# TFTBackpack.net
KiCad netlist of a schematic drawn in EAGLE
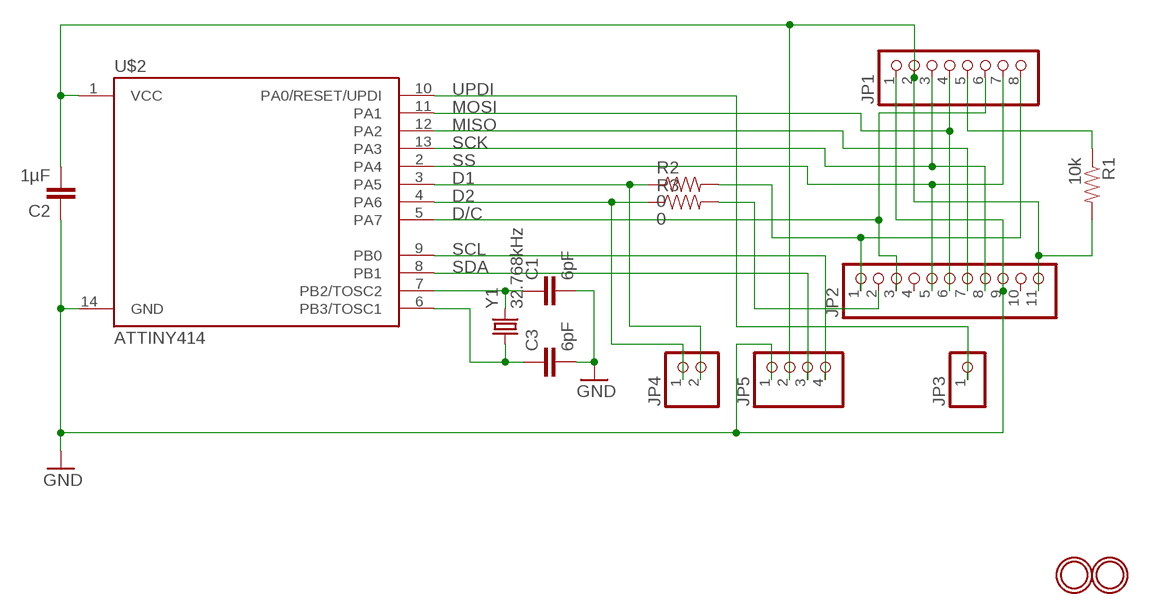
[diagram p0: schematic, sheet 1]

(export (version "E")
  (design (tool "Eeschema 10.0.6"))
  (components
    (comp (ref "C1")
      (value "6pF")
      (footprint "eagle-import:0805")
      (libsource (lib "eagle-import") (part "CAP0805"))
    )
    (comp (ref "C2")
      (value "1µF")
      (footprint "eagle-import:0805")
      (libsource (lib "eagle-import") (part "CAP0805"))
    )
    (comp (ref "C3")
      (value "6pF")
      (footprint "eagle-import:0805")
      (libsource (lib "eagle-import") (part "CAP0805"))
    )
    (comp (ref "JP1")
      (value "HEADER-1X8ROUND")
      (footprint "eagle-import:1X08_ROUND")
      (libsource (lib "eagle-import") (part "HEADER-1X8ROUND"))
    )
    (comp (ref "JP2")
      (value "HEADER-1X11")
      (footprint "eagle-import:1X11_ROUND")
      (libsource (lib "eagle-import") (part "HEADER-1X11"))
    )
    (comp (ref "JP3")
      (value "HEADER-1X1ROUND")
      (footprint "eagle-import:1X01_ROUND")
      (libsource (lib "eagle-import") (part "HEADER-1X1ROUND"))
    )
    (comp (ref "JP4")
      (value "HEADER-1X2ROUND")
      (footprint "eagle-import:1X02_ROUND")
      (libsource (lib "eagle-import") (part "HEADER-1X2ROUND"))
    )
    (comp (ref "JP5")
      (value "HEADER-1X4ROUND")
      (footprint "eagle-import:1X04_ROUND")
      (libsource (lib "eagle-import") (part "HEADER-1X4ROUND"))
    )
    (comp (ref "R1")
      (value "10k")
      (footprint "eagle-import:0805")
      (libsource (lib "eagle-import") (part "0.3OHM-1/8W-1%(0805)"))
    )
    (comp (ref "R2")
      (value "0")
      (footprint "eagle-import:0805")
      (libsource (lib "eagle-import") (part "0.3OHM-1/8W-1%(0805)"))
    )
    (comp (ref "R3")
      (value "0")
      (footprint "eagle-import:0805")
      (libsource (lib "eagle-import") (part "0.3OHM-1/8W-1%(0805)"))
    )
    (comp (ref "U$1")
      (value "MOUNTINGHOLE2.5")
      (footprint "eagle-import:MOUNTINGHOLE_2.5_PLATED")
      (libsource (lib "eagle-import") (part "MOUNTINGHOLE2.5"))
    )
    (comp (ref "U$2")
      (value "ATTINY414")
      (footprint "eagle-import:SO14")
      (libsource (lib "eagle-import") (part "ATTINY414"))
    )
    (comp (ref "U$9")
      (value "MOUNTINGHOLE2.5")
      (footprint "eagle-import:MOUNTINGHOLE_2.5_PLATED")
      (libsource (lib "eagle-import") (part "MOUNTINGHOLE2.5"))
    )
    (comp (ref "Y1")
      (value "32.768kHz")
      (footprint "eagle-import:CRYSTAL-SMD-3.2X1.5MM")
      (libsource (lib "eagle-import") (part "CRYSTAL3.2X1.5MM"))
    )
  )
  (nets
    (net (code "1") (name "/D1") (class "Default")
      (node (ref "JP4") (pin "2") (pinfunction "2_2") (pintype "passive"))
      (node (ref "R2") (pin "1") (pinfunction "1_1") (pintype "passive"))
      (node (ref "U$2") (pin "3") (pinfunction "PA5_3") (pintype "bidirectional"))
    )
    (net (code "2") (name "/D2") (class "Default")
      (node (ref "JP4") (pin "1") (pinfunction "1_1") (pintype "passive"))
      (node (ref "R3") (pin "1") (pinfunction "1_1") (pintype "passive"))
      (node (ref "U$2") (pin "4") (pinfunction "PA6_4") (pintype "bidirectional"))
    )
    (net (code "3") (name "/D{slash}C") (class "Default")
      (node (ref "JP1") (pin "6") (pinfunction "6_6") (pintype "passive"))
      (node (ref "JP2") (pin "3") (pinfunction "3_3") (pintype "passive"))
      (node (ref "U$2") (pin "5") (pinfunction "PA7_5") (pintype "bidirectional"))
    )
    (net (code "4") (name "/MISO") (class "Default")
      (node (ref "JP2") (pin "7") (pinfunction "7_7") (pintype "passive"))
      (node (ref "U$2") (pin "12") (pinfunction "PA2_12") (pintype "bidirectional"))
    )
    (net (code "5") (name "/MOSI") (class "Default")
      (node (ref "JP1") (pin "4") (pinfunction "4_4") (pintype "passive"))
      (node (ref "JP2") (pin "6") (pinfunction "6_6") (pintype "passive"))
      (node (ref "U$2") (pin "11") (pinfunction "PA1_11") (pintype "bidirectional"))
    )
    (net (code "6") (name "/SCK") (class "Default")
      (node (ref "JP1") (pin "3") (pinfunction "3_3") (pintype "passive"))
      (node (ref "JP2") (pin "8") (pinfunction "8_8") (pintype "passive"))
      (node (ref "U$2") (pin "13") (pinfunction "PA3_13") (pintype "bidirectional"))
    )
    (net (code "7") (name "/SCL") (class "Default")
      (node (ref "JP5") (pin "4") (pinfunction "4_4") (pintype "passive"))
      (node (ref "U$2") (pin "9") (pinfunction "PB0_9") (pintype "bidirectional"))
    )
    (net (code "8") (name "/SDA") (class "Default")
      (node (ref "JP5") (pin "3") (pinfunction "3_3") (pintype "passive"))
      (node (ref "U$2") (pin "8") (pinfunction "PB1_8") (pintype "bidirectional"))
    )
    (net (code "9") (name "/SS") (class "Default")
      (node (ref "JP1") (pin "7") (pinfunction "7_7") (pintype "passive"))
      (node (ref "JP2") (pin "5") (pinfunction "5_5") (pintype "passive"))
      (node (ref "U$2") (pin "2") (pinfunction "PA4_2") (pintype "bidirectional"))
    )
    (net (code "10") (name "/UPDI") (class "Default")
      (node (ref "JP3") (pin "1") (pinfunction "1_1") (pintype "passive"))
      (node (ref "U$2") (pin "10") (pinfunction "PA0/RESET/UPDI_10") (pintype "bidirectional"))
    )
    (net (code "11") (name "GND") (class "Default")
      (node (ref "C1") (pin "2") (pinfunction "2_2") (pintype "passive"))
      (node (ref "C2") (pin "1") (pinfunction "1_1") (pintype "passive"))
      (node (ref "C3") (pin "2") (pinfunction "2_2") (pintype "passive"))
      (node (ref "JP1") (pin "1") (pinfunction "1_1") (pintype "passive"))
      (node (ref "JP2") (pin "9") (pinfunction "9_9") (pintype "passive"))
      (node (ref "JP5") (pin "1") (pinfunction "1_1") (pintype "passive"))
      (node (ref "U$2") (pin "14") (pinfunction "GND_14") (pintype "bidirectional"))
    )
    (net (code "12") (name "Net-(JP1-Pad5)") (class "Default")
      (node (ref "JP1") (pin "5") (pinfunction "5_5") (pintype "passive"))
      (node (ref "R1") (pin "1") (pinfunction "1_1") (pintype "passive"))
    )
    (net (code "13") (name "Net-(JP1-Pad8)") (class "Default")
      (node (ref "JP1") (pin "8") (pinfunction "8_8") (pintype "passive"))
      (node (ref "JP2") (pin "1") (pinfunction "1_1") (pintype "passive"))
      (node (ref "R2") (pin "2") (pinfunction "2_2") (pintype "passive"))
    )
    (net (code "14") (name "Net-(JP2-Pad2)") (class "Default")
      (node (ref "JP2") (pin "2") (pinfunction "2_2") (pintype "passive"))
      (node (ref "R3") (pin "2") (pinfunction "2_2") (pintype "passive"))
    )
    (net (code "15") (name "Net-(U$2-PB2{slash}TOSC2)") (class "Default")
      (node (ref "C1") (pin "1") (pinfunction "1_1") (pintype "passive"))
      (node (ref "U$2") (pin "7") (pinfunction "PB2/TOSC2_7") (pintype "bidirectional"))
      (node (ref "Y1") (pin "P$2") (pinfunction "2_P$2") (pintype "passive"))
    )
    (net (code "16") (name "Net-(U$2-PB3{slash}TOSC1)") (class "Default")
      (node (ref "C3") (pin "1") (pinfunction "1_1") (pintype "passive"))
      (node (ref "U$2") (pin "6") (pinfunction "PB3/TOSC1_6") (pintype "bidirectional"))
      (node (ref "Y1") (pin "P$1") (pinfunction "1_P$1") (pintype "passive"))
    )
    (net (code "17") (name "Net-(U$2-VCC)") (class "Default")
      (node (ref "C2") (pin "2") (pinfunction "2_2") (pintype "passive"))
      (node (ref "JP1") (pin "2") (pinfunction "2_2") (pintype "passive"))
      (node (ref "JP2") (pin "11") (pinfunction "11_11") (pintype "passive"))
      (node (ref "JP5") (pin "2") (pinfunction "2_2") (pintype "passive"))
      (node (ref "R1") (pin "2") (pinfunction "2_2") (pintype "passive"))
      (node (ref "U$2") (pin "1") (pinfunction "VCC_1") (pintype "bidirectional"))
    )
    (net (code "18") (name "unconnected-(JP2-Pad4)") (class "Default")
      (node (ref "JP2") (pin "4") (pinfunction "4_4") (pintype "passive"))
    )
    (net (code "19") (name "unconnected-(JP2-Pad10)") (class "Default")
      (node (ref "JP2") (pin "10") (pinfunction "10_10") (pintype "passive"))
    )
  )
)
